# WN01.net
KiCad netlist of a schematic drawn in EAGLE
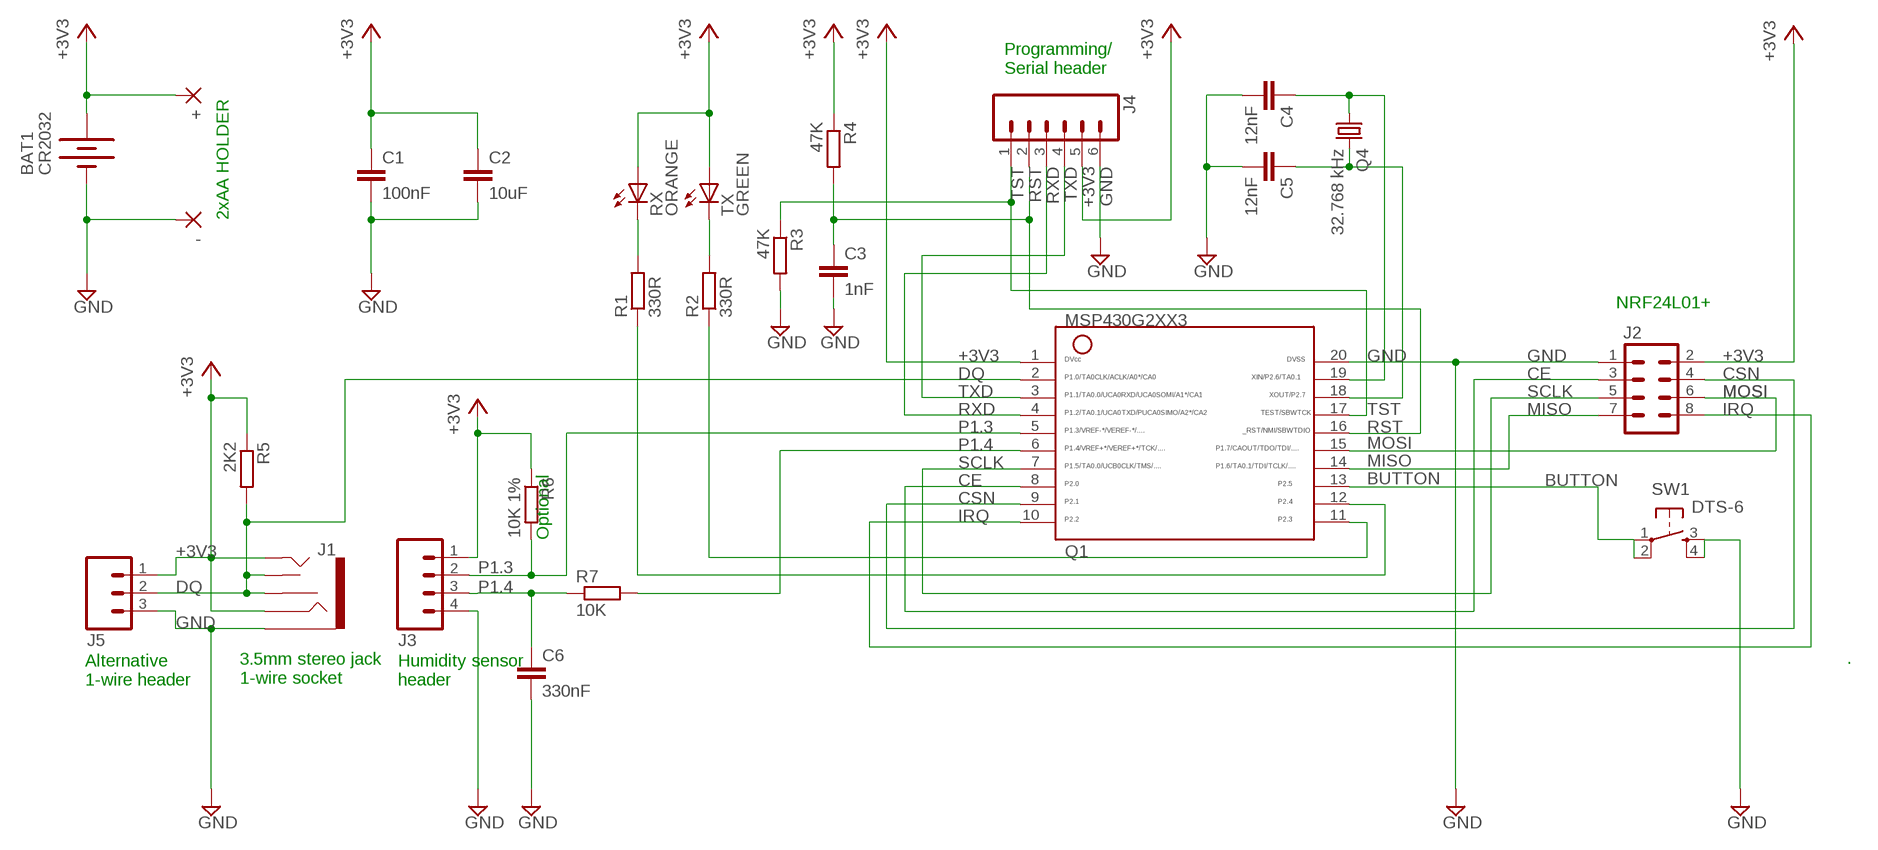
[diagram p0: schematic, sheet 1]

(export (version "E")
  (design (tool "Eeschema 10.0.6"))
  (components
    (comp (ref "+")
      (value "2,54/1,0")
      (footprint "eagle-import:2,54_1,0")
      (libsource (lib "eagle-import") (part "2,54/1,0"))
    )
    (comp (ref "-")
      (value "2,54/1,0")
      (footprint "eagle-import:2,54_1,0")
      (libsource (lib "eagle-import") (part "2,54/1,0"))
    )
    (comp (ref "BAT1")
      (value "CR2032")
      (footprint "eagle-import:BATTCOM_20MM_PTH")
      (libsource (lib "eagle-import") (part "BATTERY20PTH"))
    )
    (comp (ref "C1")
      (value "100nF")
      (footprint "eagle-import:C0805")
      (libsource (lib "eagle-import") (part "resistor_C-EUC0805"))
    )
    (comp (ref "C2")
      (value "10uF")
      (footprint "eagle-import:C1206")
      (libsource (lib "eagle-import") (part "C-EUC1206"))
    )
    (comp (ref "C3")
      (value "1nF")
      (footprint "eagle-import:C0805")
      (libsource (lib "eagle-import") (part "resistor_C-EUC0805"))
    )
    (comp (ref "C4")
      (value "12nF")
      (footprint "eagle-import:C0805")
      (libsource (lib "eagle-import") (part "resistor_C-EUC0805"))
    )
    (comp (ref "C5")
      (value "12nF")
      (footprint "eagle-import:C0805")
      (libsource (lib "eagle-import") (part "resistor_C-EUC0805"))
    )
    (comp (ref "C6")
      (value "330nF")
      (footprint "eagle-import:C0805")
      (libsource (lib "eagle-import") (part "resistor_C-EUC0805"))
    )
    (comp (ref "J1")
      (value "AUDIO-JACK2PTH")
      (footprint "eagle-import:AUDIO-JACK")
      (libsource (lib "eagle-import") (part "AUDIO-JACK2PTH"))
    )
    (comp (ref "J2")
      (value "M04X2")
      (footprint "eagle-import:2X4")
      (libsource (lib "eagle-import") (part "M04X2"))
    )
    (comp (ref "J3")
      (value "M04PTH")
      (footprint "eagle-import:1X04")
      (libsource (lib "eagle-import") (part "M04PTH"))
    )
    (comp (ref "J4")
      (value "M06SIP")
      (footprint "eagle-import:1X06")
      (libsource (lib "eagle-import") (part "M06SIP"))
    )
    (comp (ref "J5")
      (value "M03PTH")
      (footprint "eagle-import:1X03")
      (libsource (lib "eagle-import") (part "M03PTH"))
    )
    (comp (ref "Q1")
      (value "G2XX3---PW20")
      (footprint "eagle-import:PW20")
      (libsource (lib "eagle-import") (part "G2XX3---PW20"))
    )
    (comp (ref "Q4")
      (value "32.768 kHz")
      (footprint "eagle-import:TC38H")
      (libsource (lib "eagle-import") (part "CRYSTALTC38H"))
    )
    (comp (ref "R1")
      (value "330R")
      (footprint "eagle-import:M0805")
      (fields (field (name "RESISTANCE") "4K7"))
      (libsource (lib "eagle-import") (part "R-EU_M0805"))
    )
    (comp (ref "R2")
      (value "330R")
      (footprint "eagle-import:M0805")
      (fields (field (name "RESISTANCE") "4K7"))
      (libsource (lib "eagle-import") (part "R-EU_M0805"))
    )
    (comp (ref "R3")
      (value "47K")
      (footprint "eagle-import:M0805")
      (fields (field (name "RESISTANCE") "4K7"))
      (libsource (lib "eagle-import") (part "R-EU_M0805"))
    )
    (comp (ref "R4")
      (value "47K")
      (footprint "eagle-import:M0805")
      (fields (field (name "RESISTANCE") "4K7"))
      (libsource (lib "eagle-import") (part "R-EU_M0805"))
    )
    (comp (ref "R5")
      (value "2K2")
      (footprint "eagle-import:M0805")
      (fields (field (name "RESISTANCE") "4K7"))
      (libsource (lib "eagle-import") (part "R-EU_M0805"))
    )
    (comp (ref "R6")
      (value "10K 1%")
      (footprint "eagle-import:M0805")
      (fields (field (name "RESISTANCE") "4K7"))
      (libsource (lib "eagle-import") (part "R-EU_M0805"))
    )
    (comp (ref "R7")
      (value "10K")
      (footprint "eagle-import:M0805")
      (fields (field (name "RESISTANCE") "4K7"))
      (libsource (lib "eagle-import") (part "R-EU_M0805"))
    )
    (comp (ref "RX")
      (value "ORANGE")
      (footprint "eagle-import:CHIPLED_0805")
      (libsource (lib "eagle-import") (part "LEDCHIPLED_0805"))
    )
    (comp (ref "SW1")
      (value "DTS-6")
      (footprint "eagle-import:DTS-6")
      (libsource (lib "eagle-import") (part "DTS-6"))
    )
    (comp (ref "TX")
      (value "GREEN")
      (footprint "eagle-import:CHIPLED_0805")
      (libsource (lib "eagle-import") (part "LEDCHIPLED_0805"))
    )
  )
  (nets
    (net (code "1") (name "+3V3") (class "Default")
      (node (ref "+") (pin "1") (pinfunction "P_1") (pintype "passive"))
      (node (ref "BAT1") (pin "1") (pinfunction "+_1") (pintype "power_in"))
      (node (ref "C1") (pin "1") (pinfunction "1_1") (pintype "passive"))
      (node (ref "C2") (pin "1") (pinfunction "1_1") (pintype "passive"))
      (node (ref "J1") (pin "RING") (pinfunction "RING_RING") (pintype "bidirectional"))
      (node (ref "J1") (pin "TIP") (pinfunction "TIP_TIP") (pintype "bidirectional"))
      (node (ref "J2") (pin "2") (pinfunction "2_2") (pintype "passive"))
      (node (ref "J3") (pin "1") (pinfunction "1_1") (pintype "passive"))
      (node (ref "J4") (pin "5") (pinfunction "5_5") (pintype "passive"))
      (node (ref "J5") (pin "1") (pinfunction "1_1") (pintype "passive"))
      (node (ref "Q1") (pin "1") (pinfunction "1_1") (pintype "bidirectional"))
      (node (ref "R4") (pin "1") (pinfunction "1_1") (pintype "passive"))
      (node (ref "R5") (pin "1") (pinfunction "1_1") (pintype "passive"))
      (node (ref "R6") (pin "1") (pinfunction "1_1") (pintype "passive"))
      (node (ref "RX") (pin "A") (pinfunction "A_A") (pintype "passive"))
      (node (ref "TX") (pin "A") (pinfunction "A_A") (pintype "passive"))
    )
    (net (code "2") (name "/BUTTON") (class "Default")
      (node (ref "Q1") (pin "13") (pinfunction "13_13") (pintype "bidirectional"))
      (node (ref "SW1") (pin "1") (pinfunction "1_1") (pintype "passive"))
      (node (ref "SW1") (pin "2") (pinfunction "2_2") (pintype "passive"))
    )
    (net (code "3") (name "/CE") (class "Default")
      (node (ref "J2") (pin "3") (pinfunction "3_3") (pintype "passive"))
      (node (ref "Q1") (pin "8") (pinfunction "8_8") (pintype "bidirectional"))
    )
    (net (code "4") (name "/CSN") (class "Default")
      (node (ref "J2") (pin "4") (pinfunction "4_4") (pintype "passive"))
      (node (ref "Q1") (pin "9") (pinfunction "9_9") (pintype "bidirectional"))
    )
    (net (code "5") (name "/DQ") (class "Default")
      (node (ref "J1") (pin "RSH") (pinfunction "RSH_RSH") (pintype "bidirectional"))
      (node (ref "J1") (pin "TSH") (pinfunction "TSH_TSH") (pintype "bidirectional"))
      (node (ref "J5") (pin "2") (pinfunction "2_2") (pintype "passive"))
      (node (ref "Q1") (pin "2") (pinfunction "2_2") (pintype "bidirectional"))
      (node (ref "R5") (pin "2") (pinfunction "2_2") (pintype "passive"))
    )
    (net (code "6") (name "/IRQ") (class "Default")
      (node (ref "J2") (pin "8") (pinfunction "8_8") (pintype "passive"))
      (node (ref "Q1") (pin "10") (pinfunction "10_10") (pintype "bidirectional"))
    )
    (net (code "7") (name "/MISO") (class "Default")
      (node (ref "J2") (pin "7") (pinfunction "7_7") (pintype "passive"))
      (node (ref "Q1") (pin "14") (pinfunction "14_14") (pintype "bidirectional"))
    )
    (net (code "8") (name "/MOSI") (class "Default")
      (node (ref "J2") (pin "6") (pinfunction "6_6") (pintype "passive"))
      (node (ref "Q1") (pin "15") (pinfunction "15_15") (pintype "bidirectional"))
    )
    (net (code "9") (name "/P1.3") (class "Default")
      (node (ref "J3") (pin "2") (pinfunction "2_2") (pintype "passive"))
      (node (ref "Q1") (pin "5") (pinfunction "5_5") (pintype "bidirectional"))
      (node (ref "R6") (pin "2") (pinfunction "2_2") (pintype "passive"))
    )
    (net (code "10") (name "/P1.4") (class "Default")
      (node (ref "Q1") (pin "6") (pinfunction "6_6") (pintype "bidirectional"))
      (node (ref "R7") (pin "2") (pinfunction "2_2") (pintype "passive"))
    )
    (net (code "11") (name "/RST") (class "Default")
      (node (ref "C3") (pin "1") (pinfunction "1_1") (pintype "passive"))
      (node (ref "J4") (pin "2") (pinfunction "2_2") (pintype "passive"))
      (node (ref "Q1") (pin "16") (pinfunction "16_16") (pintype "bidirectional"))
      (node (ref "R4") (pin "2") (pinfunction "2_2") (pintype "passive"))
    )
    (net (code "12") (name "/RXD") (class "Default")
      (node (ref "J4") (pin "3") (pinfunction "3_3") (pintype "passive"))
      (node (ref "Q1") (pin "4") (pinfunction "4_4") (pintype "bidirectional"))
    )
    (net (code "13") (name "/SCLK") (class "Default")
      (node (ref "J2") (pin "5") (pinfunction "5_5") (pintype "passive"))
      (node (ref "Q1") (pin "7") (pinfunction "7_7") (pintype "bidirectional"))
    )
    (net (code "14") (name "/TST") (class "Default")
      (node (ref "J4") (pin "1") (pinfunction "1_1") (pintype "passive"))
      (node (ref "Q1") (pin "17") (pinfunction "17_17") (pintype "bidirectional"))
      (node (ref "R3") (pin "1") (pinfunction "1_1") (pintype "passive"))
    )
    (net (code "15") (name "/TXD") (class "Default")
      (node (ref "J4") (pin "4") (pinfunction "4_4") (pintype "passive"))
      (node (ref "Q1") (pin "3") (pinfunction "3_3") (pintype "bidirectional"))
    )
    (net (code "16") (name "GND") (class "Default")
      (node (ref "-") (pin "1") (pinfunction "P_1") (pintype "passive"))
      (node (ref "BAT1") (pin "2") (pinfunction "-_2") (pintype "power_in"))
      (node (ref "C1") (pin "2") (pinfunction "2_2") (pintype "passive"))
      (node (ref "C2") (pin "2") (pinfunction "2_2") (pintype "passive"))
      (node (ref "C3") (pin "2") (pinfunction "2_2") (pintype "passive"))
      (node (ref "C4") (pin "2") (pinfunction "2_2") (pintype "passive"))
      (node (ref "C5") (pin "2") (pinfunction "2_2") (pintype "passive"))
      (node (ref "C6") (pin "2") (pinfunction "2_2") (pintype "passive"))
      (node (ref "J1") (pin "SLEEVE") (pinfunction "SLEEVE_SLEEVE") (pintype "bidirectional"))
      (node (ref "J2") (pin "1") (pinfunction "1_1") (pintype "passive"))
      (node (ref "J3") (pin "4") (pinfunction "4_4") (pintype "passive"))
      (node (ref "J4") (pin "6") (pinfunction "6_6") (pintype "passive"))
      (node (ref "J5") (pin "3") (pinfunction "3_3") (pintype "passive"))
      (node (ref "Q1") (pin "20") (pinfunction "20_20") (pintype "bidirectional"))
      (node (ref "R3") (pin "2") (pinfunction "2_2") (pintype "passive"))
      (node (ref "SW1") (pin "3") (pinfunction "3_3") (pintype "passive"))
      (node (ref "SW1") (pin "4") (pinfunction "4_4") (pintype "passive"))
    )
    (net (code "17") (name "Net-(C4-Pad1)") (class "Default")
      (node (ref "C4") (pin "1") (pinfunction "1_1") (pintype "passive"))
      (node (ref "Q1") (pin "19") (pinfunction "19_19") (pintype "bidirectional"))
      (node (ref "Q4") (pin "1") (pinfunction "1_1") (pintype "passive"))
    )
    (net (code "18") (name "Net-(C5-Pad1)") (class "Default")
      (node (ref "C5") (pin "1") (pinfunction "1_1") (pintype "passive"))
      (node (ref "Q1") (pin "18") (pinfunction "18_18") (pintype "bidirectional"))
      (node (ref "Q4") (pin "2") (pinfunction "2_2") (pintype "passive"))
    )
    (net (code "19") (name "Net-(C6-Pad1)") (class "Default")
      (node (ref "C6") (pin "1") (pinfunction "1_1") (pintype "passive"))
      (node (ref "J3") (pin "3") (pinfunction "3_3") (pintype "passive"))
      (node (ref "R7") (pin "1") (pinfunction "1_1") (pintype "passive"))
    )
    (net (code "20") (name "Net-(Q1-Pad11)") (class "Default")
      (node (ref "Q1") (pin "11") (pinfunction "11_11") (pintype "bidirectional"))
      (node (ref "R2") (pin "1") (pinfunction "1_1") (pintype "passive"))
    )
    (net (code "21") (name "Net-(Q1-Pad12)") (class "Default")
      (node (ref "Q1") (pin "12") (pinfunction "12_12") (pintype "bidirectional"))
      (node (ref "R1") (pin "1") (pinfunction "1_1") (pintype "passive"))
    )
    (net (code "22") (name "Net-(R1-Pad2)") (class "Default")
      (node (ref "R1") (pin "2") (pinfunction "2_2") (pintype "passive"))
      (node (ref "RX") (pin "C") (pinfunction "C_C") (pintype "passive"))
    )
    (net (code "23") (name "Net-(R2-Pad2)") (class "Default")
      (node (ref "R2") (pin "2") (pinfunction "2_2") (pintype "passive"))
      (node (ref "TX") (pin "C") (pinfunction "C_C") (pintype "passive"))
    )
  )
)
